# MCU.net
KiCad netlist of a schematic drawn in Altium Designer
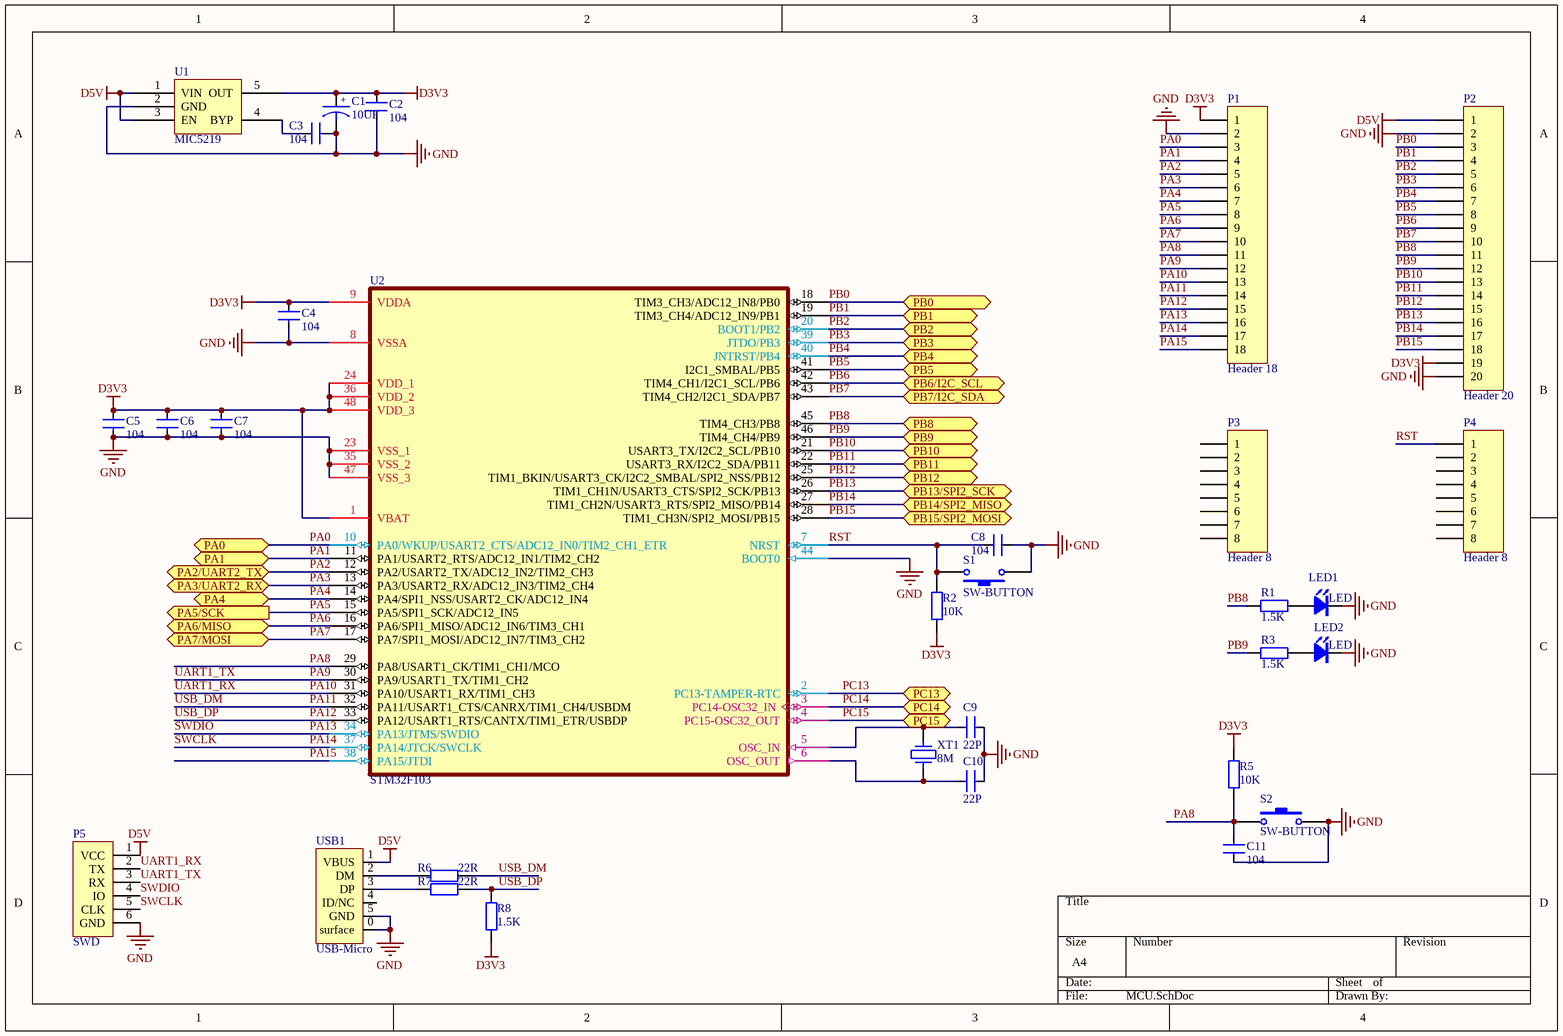
[diagram p0: MCU.SchDoc]

(export (version "E")
  (design (tool "Eeschema 10.0.6"))
  (components
    (comp (ref "C1")
      (value "10UF")
      (footprint "3216C")
      (description "钽电容")
      (libsource (lib "lib_AD") (part "CAP-T"))
    )
    (comp (ref "C2")
      (value "104")
      (footprint "0603C")
      (description "普通小电容")
      (libsource (lib "lib_GMDZ") (part "CAP"))
    )
    (comp (ref "C3")
      (value "104")
      (footprint "0603C")
      (description "普通小电容")
      (libsource (lib "lib_GMDZ") (part "CAP"))
    )
    (comp (ref "C4")
      (value "104")
      (footprint "0603C")
      (description "普通小电容")
      (libsource (lib "lib_GMDZ") (part "CAP"))
    )
    (comp (ref "C5")
      (value "104")
      (footprint "0603C")
      (description "普通小电容")
      (libsource (lib "lib_GMDZ") (part "CAP"))
    )
    (comp (ref "C6")
      (value "104")
      (footprint "0603C")
      (description "普通小电容")
      (libsource (lib "lib_GMDZ") (part "CAP"))
    )
    (comp (ref "C7")
      (value "104")
      (footprint "0603C")
      (description "普通小电容")
      (libsource (lib "lib_GMDZ") (part "CAP"))
    )
    (comp (ref "C8")
      (value "104")
      (footprint "0603C")
      (description "普通小电容")
      (libsource (lib "lib_AD") (part "CAP"))
    )
    (comp (ref "C9")
      (value "22P")
      (footprint "0603C")
      (description "普通小电容")
      (libsource (lib "lib_AD") (part "CAP"))
    )
    (comp (ref "C10")
      (value "22P")
      (footprint "0603C")
      (description "普通小电容")
      (libsource (lib "lib_AD") (part "CAP"))
    )
    (comp (ref "C11")
      (value "104")
      (footprint "0603C")
      (description "普通小电容")
      (libsource (lib "lib_AD") (part "CAP"))
    )
    (comp (ref "LED1") (value "LED") (footprint "0805D") (libsource (lib "lib_AD") (part "LED")))
    (comp (ref "LED2") (value "LED") (footprint "0805D") (libsource (lib "lib_AD") (part "LED")))
    (comp (ref "P1")
      (value "Header 18")
      (footprint "HDR1X18")
      (description "Header, 18-Pin")
      (fields (field (name "PUBLISHER") "Altium Limited"))
      (libsource (lib "lib_AD") (part "Header 18"))
    )
    (comp (ref "P2")
      (value "Header 20")
      (footprint "HDR1X20")
      (description "Header, 20-Pin")
      (fields (field (name "PUBLISHER") "Altium Limited"))
      (libsource (lib "lib_AD") (part "Header 20"))
    )
    (comp (ref "P3")
      (value "Header 8")
      (footprint "HDR1X8")
      (description "Header, 8-Pin")
      (fields (field (name "PUBLISHER") "Altium Limited"))
      (libsource (lib "lib_AD") (part "Header 8"))
    )
    (comp (ref "P4")
      (value "Header 8")
      (footprint "HDR1X8")
      (description "Header, 8-Pin")
      (fields (field (name "PUBLISHER") "Altium Limited"))
      (libsource (lib "lib_AD") (part "Header 8"))
    )
    (comp (ref "P5")
      (value "SWD")
      (footprint "HDR1X6")
      (description "单片机端")
      (libsource (lib "lib_AD") (part "SWD"))
    )
    (comp (ref "R1")
      (value "1.5K")
      (footprint "0603R")
      (description "普通电阻")
      (libsource (lib "") (part "RES_1"))
    )
    (comp (ref "R2")
      (value "10K")
      (footprint "0603R")
      (description "普通电阻")
      (libsource (lib "") (part "RES_3"))
    )
    (comp (ref "R3")
      (value "1.5K")
      (footprint "0603R")
      (description "普通电阻")
      (libsource (lib "") (part "RES_1"))
    )
    (comp (ref "R5")
      (value "10K")
      (footprint "0603R")
      (description "普通电阻")
      (libsource (lib "") (part "RES_2"))
    )
    (comp (ref "R6")
      (value "22R")
      (footprint "0603R")
      (description "普通电阻")
      (libsource (lib "lib_AD") (part "RES"))
    )
    (comp (ref "R7")
      (value "22R")
      (footprint "0603R")
      (description "普通电阻")
      (libsource (lib "lib_AD") (part "RES"))
    )
    (comp (ref "R8")
      (value "1.5K")
      (footprint "0603R")
      (description "普通电阻")
      (libsource (lib "") (part "RES_2"))
    )
    (comp (ref "S1") (value "SW-BUTTON") (footprint "SW-KEY") (libsource (lib "lib_AD") (part "SW-BUTTON")))
    (comp (ref "S2") (value "SW-BUTTON") (footprint "SW-KEY") (libsource (lib "lib_AD") (part "SW-BUTTON")))
    (comp (ref "U1") (value "MIC5219") (footprint "SOT23-5") (libsource (lib "lib_GMDZ") (part "MIC5219")))
    (comp (ref "U2") (value "STM32F103") (footprint "LQFP48") (libsource (lib "lib_GMDZ") (part "STM32F103")))
    (comp (ref "USB1")
      (value "USB-Micro")
      (footprint "USB-Micro-2")
      (description "USB 1.1, Right Angle, SMT, A Type, Plug, 4 Position, Natural")
      (fields (field (name "PUBLISHER") "Altium Limited"))
      (libsource (lib "lib_AD") (part "USB-Micro"))
    )
    (comp (ref "XT1")
      (value "8M")
      (footprint "5032")
      (description "晶振")
      (libsource (lib "lib_GMDZ") (part "XT"))
    )
  )
  (nets
    (net (code "4") (name "/PA0") (class "Default")
      (node (ref "P1") (pin "3") (pinfunction "3_3") (pintype "passive"))
      (node (ref "U2") (pin "10") (pinfunction "PA0/WKUP/USART2_CTS/ADC12_IN0/TIM2_CH1_ETR_10") (pintype "bidirectional"))
    )
    (net (code "5") (name "/PA1") (class "Default")
      (node (ref "P1") (pin "4") (pinfunction "4_4") (pintype "passive"))
      (node (ref "U2") (pin "11") (pinfunction "PA1/USART2_RTS/ADC12_IN1/TIM2_CH2_11") (pintype "bidirectional"))
    )
    (net (code "6") (name "/PA2") (class "Default")
      (node (ref "P1") (pin "5") (pinfunction "5_5") (pintype "passive"))
      (node (ref "U2") (pin "12") (pinfunction "PA2/USART2_TX/ADC12_IN2/TIM2_CH3_12") (pintype "bidirectional"))
    )
    (net (code "7") (name "/PA3") (class "Default")
      (node (ref "P1") (pin "6") (pinfunction "6_6") (pintype "passive"))
      (node (ref "U2") (pin "13") (pinfunction "PA3/USART2_RX/ADC12_IN3/TIM2_CH4_13") (pintype "bidirectional"))
    )
    (net (code "8") (name "/PA4") (class "Default")
      (node (ref "P1") (pin "7") (pinfunction "7_7") (pintype "passive"))
      (node (ref "U2") (pin "14") (pinfunction "PA4/SPI1_NSS/USART2_CK/ADC12_IN4_14") (pintype "bidirectional"))
    )
    (net (code "9") (name "/PA5") (class "Default")
      (node (ref "P1") (pin "8") (pinfunction "8_8") (pintype "passive"))
      (node (ref "U2") (pin "15") (pinfunction "PA5/SPI1_SCK/ADC12_IN5_15") (pintype "bidirectional"))
    )
    (net (code "10") (name "/PA6") (class "Default")
      (node (ref "P1") (pin "9") (pinfunction "9_9") (pintype "passive"))
      (node (ref "U2") (pin "16") (pinfunction "PA6/SPI1_MISO/ADC12_IN6/TIM3_CH1_16") (pintype "bidirectional"))
    )
    (net (code "11") (name "/PA7") (class "Default")
      (node (ref "P1") (pin "10") (pinfunction "10_10") (pintype "passive"))
      (node (ref "U2") (pin "17") (pinfunction "PA7/SPI1_MOSI/ADC12_IN7/TIM3_CH2_17") (pintype "bidirectional"))
    )
    (net (code "12") (name "/PA8") (class "Default")
      (node (ref "C11") (pin "2") (pinfunction "2_2") (pintype "passive"))
      (node (ref "P1") (pin "11") (pinfunction "11_11") (pintype "passive"))
      (node (ref "R5") (pin "2") (pinfunction "2_2") (pintype "passive"))
      (node (ref "S2") (pin "1") (pinfunction "1_1") (pintype "passive"))
      (node (ref "U2") (pin "29") (pinfunction "PA8/USART1_CK/TIM1_CH1/MCO_29") (pintype "bidirectional"))
    )
    (net (code "13") (name "/PA9") (class "Default")
      (node (ref "P1") (pin "12") (pinfunction "12_12") (pintype "passive"))
      (node (ref "P5") (pin "3") (pinfunction "RX_3") (pintype "passive"))
      (node (ref "U2") (pin "30") (pinfunction "PA9/USART1_TX/TIM1_CH2_30") (pintype "bidirectional"))
    )
    (net (code "14") (name "/PA10") (class "Default")
      (node (ref "P1") (pin "13") (pinfunction "13_13") (pintype "passive"))
      (node (ref "P5") (pin "2") (pinfunction "TX_2") (pintype "passive"))
      (node (ref "U2") (pin "31") (pinfunction "PA10/USART1_RX/TIM1_CH3_31") (pintype "bidirectional"))
    )
    (net (code "15") (name "/PA11") (class "Default")
      (node (ref "P1") (pin "14") (pinfunction "14_14") (pintype "passive"))
      (node (ref "R6") (pin "1") (pinfunction "1_1") (pintype "passive"))
      (node (ref "U2") (pin "32") (pinfunction "PA11/USART1_CTS/CANRX/TIM1_CH4/USBDM_32") (pintype "bidirectional"))
    )
    (net (code "16") (name "/PA12") (class "Default")
      (node (ref "P1") (pin "15") (pinfunction "15_15") (pintype "passive"))
      (node (ref "R7") (pin "1") (pinfunction "1_1") (pintype "passive"))
      (node (ref "R8") (pin "1") (pinfunction "1_1") (pintype "passive"))
      (node (ref "U2") (pin "33") (pinfunction "PA12/USART1_RTS/CANTX/TIM1_ETR/USBDP_33") (pintype "bidirectional"))
    )
    (net (code "17") (name "/PA13") (class "Default")
      (node (ref "P1") (pin "16") (pinfunction "16_16") (pintype "passive"))
      (node (ref "P5") (pin "4") (pinfunction "IO_4") (pintype "passive"))
      (node (ref "U2") (pin "34") (pinfunction "PA13/JTMS/SWDIO_34") (pintype "bidirectional"))
    )
    (net (code "18") (name "/PA14") (class "Default")
      (node (ref "P1") (pin "17") (pinfunction "17_17") (pintype "passive"))
      (node (ref "P5") (pin "5") (pinfunction "CLK_5") (pintype "passive"))
      (node (ref "U2") (pin "37") (pinfunction "PA14/JTCK/SWCLK_37") (pintype "bidirectional"))
    )
    (net (code "19") (name "/PA15") (class "Default")
      (node (ref "P1") (pin "18") (pinfunction "18_18") (pintype "passive"))
      (node (ref "U2") (pin "38") (pinfunction "PA15/JTDI_38") (pintype "bidirectional"))
    )
    (net (code "20") (name "/PB0") (class "Default")
      (node (ref "P2") (pin "3") (pinfunction "3_3") (pintype "passive"))
      (node (ref "U2") (pin "18") (pinfunction "TIM3_CH3/ADC12_IN8/PB0_18") (pintype "bidirectional"))
    )
    (net (code "21") (name "/PB1") (class "Default")
      (node (ref "P2") (pin "4") (pinfunction "4_4") (pintype "passive"))
      (node (ref "U2") (pin "19") (pinfunction "TIM3_CH4/ADC12_IN9/PB1_19") (pintype "bidirectional"))
    )
    (net (code "22") (name "/PB2") (class "Default")
      (node (ref "P2") (pin "5") (pinfunction "5_5") (pintype "passive"))
      (node (ref "U2") (pin "20") (pinfunction "BOOT1/PB2_20") (pintype "bidirectional"))
    )
    (net (code "23") (name "/PB3") (class "Default")
      (node (ref "P2") (pin "6") (pinfunction "6_6") (pintype "passive"))
      (node (ref "U2") (pin "39") (pinfunction "JTDO/PB3_39") (pintype "bidirectional"))
    )
    (net (code "24") (name "/PB4") (class "Default")
      (node (ref "P2") (pin "7") (pinfunction "7_7") (pintype "passive"))
      (node (ref "U2") (pin "40") (pinfunction "JNTRST/PB4_40") (pintype "bidirectional"))
    )
    (net (code "25") (name "/PB5") (class "Default")
      (node (ref "P2") (pin "8") (pinfunction "8_8") (pintype "passive"))
      (node (ref "U2") (pin "41") (pinfunction "I2C1_SMBAL/PB5_41") (pintype "bidirectional"))
    )
    (net (code "26") (name "/PB6") (class "Default")
      (node (ref "P2") (pin "9") (pinfunction "9_9") (pintype "passive"))
      (node (ref "U2") (pin "42") (pinfunction "TIM4_CH1/I2C1_SCL/PB6_42") (pintype "bidirectional"))
    )
    (net (code "27") (name "/PB7") (class "Default")
      (node (ref "P2") (pin "10") (pinfunction "10_10") (pintype "passive"))
      (node (ref "U2") (pin "43") (pinfunction "TIM4_CH2/I2C1_SDA/PB7_43") (pintype "bidirectional"))
    )
    (net (code "28") (name "/PB8") (class "Default")
      (node (ref "P2") (pin "11") (pinfunction "11_11") (pintype "passive"))
      (node (ref "R1") (pin "1") (pinfunction "1_1") (pintype "passive"))
      (node (ref "U2") (pin "45") (pinfunction "TIM4_CH3/PB8_45") (pintype "bidirectional"))
    )
    (net (code "29") (name "/PB9") (class "Default")
      (node (ref "P2") (pin "12") (pinfunction "12_12") (pintype "passive"))
      (node (ref "R3") (pin "1") (pinfunction "1_1") (pintype "passive"))
      (node (ref "U2") (pin "46") (pinfunction "TIM4_CH4/PB9_46") (pintype "bidirectional"))
    )
    (net (code "30") (name "/PB10") (class "Default")
      (node (ref "P2") (pin "13") (pinfunction "13_13") (pintype "passive"))
      (node (ref "U2") (pin "21") (pinfunction "USART3_TX/I2C2_SCL/PB10_21") (pintype "bidirectional"))
    )
    (net (code "31") (name "/PB11") (class "Default")
      (node (ref "P2") (pin "14") (pinfunction "14_14") (pintype "passive"))
      (node (ref "U2") (pin "22") (pinfunction "USART3_RX/I2C2_SDA/PB11_22") (pintype "bidirectional"))
    )
    (net (code "32") (name "/PB12") (class "Default")
      (node (ref "P2") (pin "15") (pinfunction "15_15") (pintype "passive"))
      (node (ref "U2") (pin "25") (pinfunction "TIM1_BKIN/USART3_CK/I2C2_SMBAL/SPI2_NSS/PB12_25") (pintype "bidirectional"))
    )
    (net (code "33") (name "/PB13") (class "Default")
      (node (ref "P2") (pin "16") (pinfunction "16_16") (pintype "passive"))
      (node (ref "U2") (pin "26") (pinfunction "TIM1_CH1N/USART3_CTS/SPI2_SCK/PB13_26") (pintype "bidirectional"))
    )
    (net (code "34") (name "/PB14") (class "Default")
      (node (ref "P2") (pin "17") (pinfunction "17_17") (pintype "passive"))
      (node (ref "U2") (pin "27") (pinfunction "TIM1_CH2N/USART3_RTS/SPI2_MISO/PB14_27") (pintype "bidirectional"))
    )
    (net (code "35") (name "/PB15") (class "Default")
      (node (ref "P2") (pin "18") (pinfunction "18_18") (pintype "passive"))
      (node (ref "U2") (pin "28") (pinfunction "TIM1_CH3N/SPI2_MOSI/PB15_28") (pintype "bidirectional"))
    )
    (net (code "36") (name "/PC13") (class "Default")
      (node (ref "U2") (pin "2") (pinfunction "PC13-TAMPER-RTC_2") (pintype "bidirectional"))
    )
    (net (code "37") (name "/PC14") (class "Default")
      (node (ref "U2") (pin "3") (pinfunction "PC14-OSC32_IN_3") (pintype "bidirectional"))
    )
    (net (code "38") (name "/PC15") (class "Default")
      (node (ref "U2") (pin "4") (pinfunction "PC15-OSC32_OUT_4") (pintype "bidirectional"))
    )
    (net (code "39") (name "/RST") (class "Default")
      (node (ref "C8") (pin "1") (pinfunction "1_1") (pintype "passive"))
      (node (ref "P4") (pin "1") (pinfunction "1_1") (pintype "passive"))
      (node (ref "R2") (pin "2") (pinfunction "2_2") (pintype "passive"))
      (node (ref "S1") (pin "2") (pinfunction "2_2") (pintype "passive"))
      (node (ref "U2") (pin "7") (pinfunction "NRST_7") (pintype "bidirectional"))
    )
    (net (code "40") (name "D3V3") (class "Default")
      (node (ref "C1") (pin "1") (pinfunction "1_1") (pintype "passive"))
      (node (ref "C2") (pin "2") (pinfunction "2_2") (pintype "passive"))
      (node (ref "C4") (pin "2") (pinfunction "2_2") (pintype "passive"))
      (node (ref "C5") (pin "2") (pinfunction "2_2") (pintype "passive"))
      (node (ref "C6") (pin "1") (pinfunction "1_1") (pintype "passive"))
      (node (ref "C7") (pin "2") (pinfunction "2_2") (pintype "passive"))
      (node (ref "P1") (pin "1") (pinfunction "1_1") (pintype "passive"))
      (node (ref "P2") (pin "19") (pinfunction "19_19") (pintype "passive"))
      (node (ref "R2") (pin "1") (pinfunction "1_1") (pintype "passive"))
      (node (ref "R5") (pin "1") (pinfunction "1_1") (pintype "passive"))
      (node (ref "R8") (pin "2") (pinfunction "2_2") (pintype "passive"))
      (node (ref "U1") (pin "5") (pinfunction "OUT_5") (pintype "passive"))
      (node (ref "U2") (pin "1") (pinfunction "VBAT_1") (pintype "power_in"))
      (node (ref "U2") (pin "24") (pinfunction "VDD_1_24") (pintype "power_in"))
      (node (ref "U2") (pin "36") (pinfunction "VDD_2_36") (pintype "power_in"))
      (node (ref "U2") (pin "48") (pinfunction "VDD_3_48") (pintype "power_in"))
      (node (ref "U2") (pin "9") (pinfunction "VDDA_9") (pintype "power_in"))
    )
    (net (code "41") (name "D5V") (class "Default")
      (node (ref "P2") (pin "1") (pinfunction "1_1") (pintype "passive"))
      (node (ref "P5") (pin "1") (pinfunction "VCC_1") (pintype "passive"))
      (node (ref "U1") (pin "1") (pinfunction "VIN_1") (pintype "passive"))
      (node (ref "U1") (pin "3") (pinfunction "EN_3") (pintype "passive"))
      (node (ref "USB1") (pin "1") (pinfunction "VBUS_1") (pintype "power_in"))
    )
    (net (code "42") (name "GND") (class "Default")
      (node (ref "C1") (pin "2") (pinfunction "2_2") (pintype "passive"))
      (node (ref "C10") (pin "2") (pinfunction "2_2") (pintype "passive"))
      (node (ref "C11") (pin "1") (pinfunction "1_1") (pintype "passive"))
      (node (ref "C2") (pin "1") (pinfunction "1_1") (pintype "passive"))
      (node (ref "C3") (pin "2") (pinfunction "2_2") (pintype "passive"))
      (node (ref "C4") (pin "1") (pinfunction "1_1") (pintype "passive"))
      (node (ref "C5") (pin "1") (pinfunction "1_1") (pintype "passive"))
      (node (ref "C6") (pin "2") (pinfunction "2_2") (pintype "passive"))
      (node (ref "C7") (pin "1") (pinfunction "1_1") (pintype "passive"))
      (node (ref "C8") (pin "2") (pinfunction "2_2") (pintype "passive"))
      (node (ref "C9") (pin "2") (pinfunction "2_2") (pintype "passive"))
      (node (ref "LED1") (pin "K") (pinfunction "2_K") (pintype "passive"))
      (node (ref "LED2") (pin "K") (pinfunction "2_K") (pintype "passive"))
      (node (ref "P1") (pin "2") (pinfunction "2_2") (pintype "passive"))
      (node (ref "P2") (pin "2") (pinfunction "2_2") (pintype "passive"))
      (node (ref "P2") (pin "20") (pinfunction "20_20") (pintype "passive"))
      (node (ref "P5") (pin "6") (pinfunction "GND_6") (pintype "passive"))
      (node (ref "S1") (pin "1") (pinfunction "1_1") (pintype "passive"))
      (node (ref "S2") (pin "2") (pinfunction "2_2") (pintype "passive"))
      (node (ref "U1") (pin "2") (pinfunction "GND_2") (pintype "passive"))
      (node (ref "U2") (pin "23") (pinfunction "VSS_1_23") (pintype "power_in"))
      (node (ref "U2") (pin "35") (pinfunction "VSS_2_35") (pintype "power_in"))
      (node (ref "U2") (pin "44") (pinfunction "BOOT0_44") (pintype "input"))
      (node (ref "U2") (pin "47") (pinfunction "VSS_3_47") (pintype "power_in"))
      (node (ref "U2") (pin "8") (pinfunction "VSSA_8") (pintype "power_in"))
      (node (ref "USB1") (pin "0") (pinfunction "surface_0") (pintype "passive"))
      (node (ref "USB1") (pin "5") (pinfunction "GND_5") (pintype "power_in"))
    )
    (net (code "43") (name "Net-(LED1-1)") (class "Default")
      (node (ref "LED1") (pin "A") (pinfunction "1_A") (pintype "passive"))
      (node (ref "R1") (pin "2") (pinfunction "2_2") (pintype "passive"))
    )
    (net (code "44") (name "Net-(LED2-1)") (class "Default")
      (node (ref "LED2") (pin "A") (pinfunction "1_A") (pintype "passive"))
      (node (ref "R3") (pin "2") (pinfunction "2_2") (pintype "passive"))
    )
    (net (code "45") (name "Net-(U1-BYP)") (class "Default")
      (node (ref "C3") (pin "1") (pinfunction "1_1") (pintype "passive"))
      (node (ref "U1") (pin "4") (pinfunction "BYP_4") (pintype "passive"))
    )
    (net (code "46") (name "Net-(U2-OSC_IN)") (class "Default")
      (node (ref "C9") (pin "1") (pinfunction "1_1") (pintype "passive"))
      (node (ref "U2") (pin "5") (pinfunction "OSC_IN_5") (pintype "input"))
      (node (ref "XT1") (pin "1") (pinfunction "1_1") (pintype "passive"))
    )
    (net (code "47") (name "Net-(U2-OSC_OUT)") (class "Default")
      (node (ref "C10") (pin "1") (pinfunction "1_1") (pintype "passive"))
      (node (ref "U2") (pin "6") (pinfunction "OSC_OUT_6") (pintype "output"))
      (node (ref "XT1") (pin "2") (pinfunction "2_2") (pintype "passive"))
    )
    (net (code "48") (name "Net-(USB1-DM)") (class "Default")
      (node (ref "R6") (pin "2") (pinfunction "2_2") (pintype "passive"))
      (node (ref "USB1") (pin "2") (pinfunction "DM_2") (pintype "passive"))
    )
    (net (code "49") (name "Net-(USB1-DP)") (class "Default")
      (node (ref "R7") (pin "2") (pinfunction "2_2") (pintype "passive"))
      (node (ref "USB1") (pin "3") (pinfunction "DP_3") (pintype "passive"))
    )
    (net (code "50") (name "unconnected-(P3-Pad1)") (class "Default")
      (node (ref "P3") (pin "1") (pinfunction "1_1") (pintype "passive"))
    )
    (net (code "51") (name "unconnected-(P3-Pad2)") (class "Default")
      (node (ref "P3") (pin "2") (pinfunction "2_2") (pintype "passive"))
    )
    (net (code "52") (name "unconnected-(P3-Pad3)") (class "Default")
      (node (ref "P3") (pin "3") (pinfunction "3_3") (pintype "passive"))
    )
    (net (code "53") (name "unconnected-(P3-Pad4)") (class "Default")
      (node (ref "P3") (pin "4") (pinfunction "4_4") (pintype "passive"))
    )
    (net (code "54") (name "unconnected-(P3-Pad5)") (class "Default")
      (node (ref "P3") (pin "5") (pinfunction "5_5") (pintype "passive"))
    )
    (net (code "55") (name "unconnected-(P3-Pad6)") (class "Default")
      (node (ref "P3") (pin "6") (pinfunction "6_6") (pintype "passive"))
    )
    (net (code "56") (name "unconnected-(P3-Pad7)") (class "Default")
      (node (ref "P3") (pin "7") (pinfunction "7_7") (pintype "passive"))
    )
    (net (code "57") (name "unconnected-(P3-Pad8)") (class "Default")
      (node (ref "P3") (pin "8") (pinfunction "8_8") (pintype "passive"))
    )
    (net (code "58") (name "unconnected-(P4-Pad2)") (class "Default")
      (node (ref "P4") (pin "2") (pinfunction "2_2") (pintype "passive"))
    )
    (net (code "59") (name "unconnected-(P4-Pad3)") (class "Default")
      (node (ref "P4") (pin "3") (pinfunction "3_3") (pintype "passive"))
    )
    (net (code "60") (name "unconnected-(P4-Pad4)") (class "Default")
      (node (ref "P4") (pin "4") (pinfunction "4_4") (pintype "passive"))
    )
    (net (code "61") (name "unconnected-(P4-Pad5)") (class "Default")
      (node (ref "P4") (pin "5") (pinfunction "5_5") (pintype "passive"))
    )
    (net (code "62") (name "unconnected-(P4-Pad6)") (class "Default")
      (node (ref "P4") (pin "6") (pinfunction "6_6") (pintype "passive"))
    )
    (net (code "63") (name "unconnected-(P4-Pad7)") (class "Default")
      (node (ref "P4") (pin "7") (pinfunction "7_7") (pintype "passive"))
    )
    (net (code "64") (name "unconnected-(P4-Pad8)") (class "Default")
      (node (ref "P4") (pin "8") (pinfunction "8_8") (pintype "passive"))
    )
    (net (code "65") (name "unconnected-(USB1-ID{slash}NC-Pad4)") (class "Default")
      (node (ref "USB1") (pin "4") (pinfunction "ID/NC_4") (pintype "passive"))
    )
  )
)
